# USB_Hub.net
KiCad netlist of a schematic drawn in Altium Designer
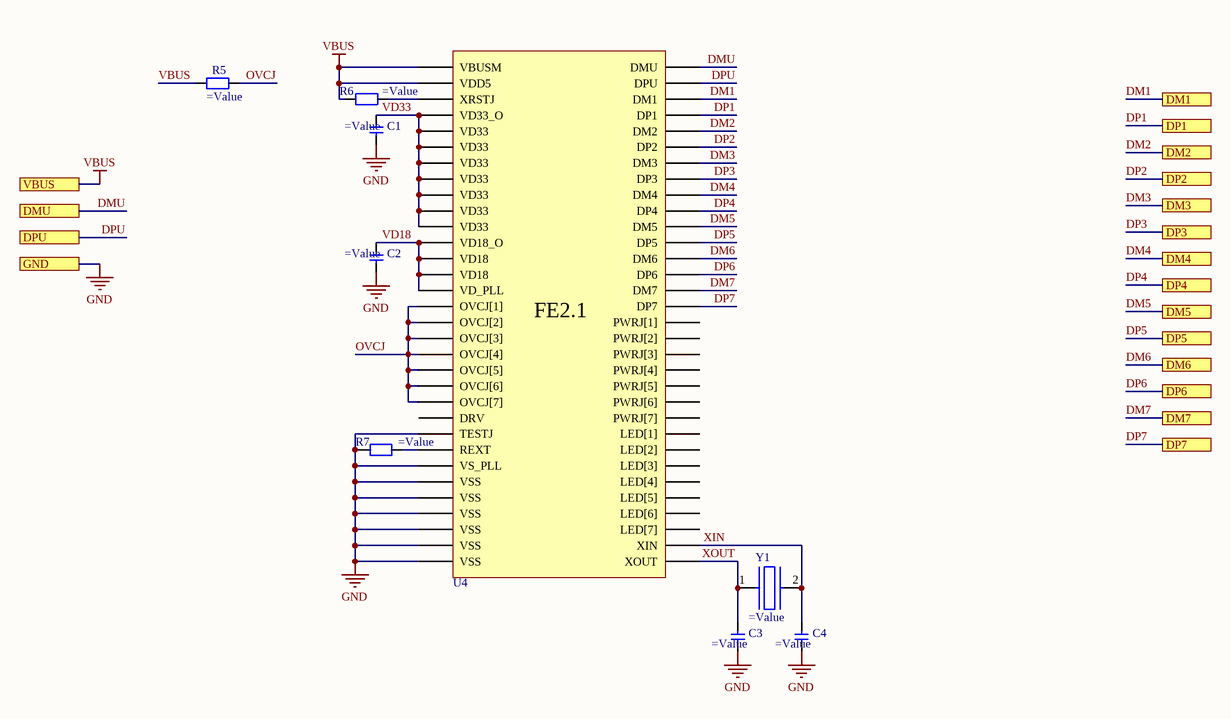
[diagram p0: USB Hub.SchDoc]

(export (version "E")
  (design (tool "Eeschema 10.0.6"))
  (components
    (comp (ref "C1") (value "~") (footprint "cap0402") (libsource (lib "AlexChistiakov") (part "Cap SMD")))
    (comp (ref "C2") (value "~") (footprint "cap0402") (libsource (lib "AlexChistiakov") (part "Cap SMD")))
    (comp (ref "C3") (value "~") (footprint "cap0402") (libsource (lib "AlexChistiakov") (part "Cap SMD")))
    (comp (ref "C4") (value "~") (footprint "cap0402") (libsource (lib "AlexChistiakov") (part "Cap SMD")))
    (comp (ref "R5")
      (value "~")
      (footprint "res0402")
      (libsource (lib "AlexChistiakov") (part "Resistor SMD"))
    )
    (comp (ref "R6")
      (value "~")
      (footprint "res0402")
      (libsource (lib "AlexChistiakov") (part "Resistor SMD"))
    )
    (comp (ref "R7")
      (value "~")
      (footprint "res0402")
      (libsource (lib "AlexChistiakov") (part "Resistor SMD"))
    )
    (comp (ref "U4")
      (value "FE2.1")
      (footprint "LQFP64_N_1")
      (libsource (lib "AlexChistiakov") (part "FE2.1"))
    )
    (comp (ref "Y1")
      (value "~")
      (footprint "QSMD3.2x2.5_A")
      (libsource (lib "AlexChistiakov") (part "Quartz"))
    )
  )
  (nets
    (net (code "1") (name "/DM1") (class "Default")
      (node (ref "U4") (pin "26") (pinfunction "DM1_26") (pintype "passive"))
    )
    (net (code "2") (name "/DM2") (class "Default")
      (node (ref "U4") (pin "23") (pinfunction "DM2_23") (pintype "passive"))
    )
    (net (code "3") (name "/DM3") (class "Default")
      (node (ref "U4") (pin "20") (pinfunction "DM3_20") (pintype "passive"))
    )
    (net (code "4") (name "/DM4") (class "Default")
      (node (ref "U4") (pin "17") (pinfunction "DM4_17") (pintype "passive"))
    )
    (net (code "5") (name "/DM5") (class "Default")
      (node (ref "U4") (pin "41") (pinfunction "DM5_41") (pintype "passive"))
    )
    (net (code "6") (name "/DM6") (class "Default")
      (node (ref "U4") (pin "44") (pinfunction "DM6_44") (pintype "passive"))
    )
    (net (code "7") (name "/DM7") (class "Default")
      (node (ref "U4") (pin "47") (pinfunction "DM7_47") (pintype "passive"))
    )
    (net (code "8") (name "/DMU") (class "Default")
      (node (ref "U4") (pin "38") (pinfunction "DMU_38") (pintype "passive"))
    )
    (net (code "9") (name "/DP1") (class "Default")
      (node (ref "U4") (pin "27") (pinfunction "DP1_27") (pintype "passive"))
    )
    (net (code "10") (name "/DP2") (class "Default")
      (node (ref "U4") (pin "24") (pinfunction "DP2_24") (pintype "passive"))
    )
    (net (code "11") (name "/DP3") (class "Default")
      (node (ref "U4") (pin "21") (pinfunction "DP3_21") (pintype "passive"))
    )
    (net (code "12") (name "/DP4") (class "Default")
      (node (ref "U4") (pin "18") (pinfunction "DP4_18") (pintype "passive"))
    )
    (net (code "13") (name "/DP5") (class "Default")
      (node (ref "U4") (pin "42") (pinfunction "DP5_42") (pintype "passive"))
    )
    (net (code "14") (name "/DP6") (class "Default")
      (node (ref "U4") (pin "45") (pinfunction "DP6_45") (pintype "passive"))
    )
    (net (code "15") (name "/DP7") (class "Default")
      (node (ref "U4") (pin "48") (pinfunction "DP7_48") (pintype "passive"))
    )
    (net (code "16") (name "/DPU") (class "Default")
      (node (ref "U4") (pin "39") (pinfunction "DPU_39") (pintype "passive"))
    )
    (net (code "17") (name "/OVCJ") (class "Default")
      (node (ref "R5") (pin "2") (pinfunction "2_2") (pintype "passive"))
      (node (ref "U4") (pin "13") (pinfunction "OVCJ[3]_13") (pintype "passive"))
      (node (ref "U4") (pin "15") (pinfunction "OVCJ[4]_15") (pintype "passive"))
      (node (ref "U4") (pin "53") (pinfunction "OVCJ[7]_53") (pintype "passive"))
      (node (ref "U4") (pin "55") (pinfunction "OVCJ[6]_55") (pintype "passive"))
      (node (ref "U4") (pin "58") (pinfunction "OVCJ[5]_58") (pintype "passive"))
      (node (ref "U4") (pin "60") (pinfunction "OVCJ[1]_60") (pintype "passive"))
      (node (ref "U4") (pin "62") (pinfunction "OVCJ[2]_62") (pintype "passive"))
    )
    (net (code "18") (name "/VD18") (class "Default")
      (node (ref "C2") (pin "2") (pinfunction "2_2") (pintype "passive"))
      (node (ref "U4") (pin "29") (pinfunction "VD_PLL_29") (pintype "passive"))
      (node (ref "U4") (pin "33") (pinfunction "VD18_O_33") (pintype "passive"))
      (node (ref "U4") (pin "36") (pinfunction "VD18_36") (pintype "passive"))
      (node (ref "U4") (pin "7") (pinfunction "VD18_7") (pintype "passive"))
    )
    (net (code "19") (name "/VD33") (class "Default")
      (node (ref "C1") (pin "2") (pinfunction "2_2") (pintype "passive"))
      (node (ref "U4") (pin "10") (pinfunction "VD33_O_10") (pintype "passive"))
      (node (ref "U4") (pin "16") (pinfunction "VD33_16") (pintype "passive"))
      (node (ref "U4") (pin "22") (pinfunction "VD33_22") (pintype "passive"))
      (node (ref "U4") (pin "28") (pinfunction "VD33_28") (pintype "passive"))
      (node (ref "U4") (pin "34") (pinfunction "VD33_34") (pintype "passive"))
      (node (ref "U4") (pin "40") (pinfunction "VD33_40") (pintype "passive"))
      (node (ref "U4") (pin "46") (pinfunction "VD33_46") (pintype "passive"))
      (node (ref "U4") (pin "56") (pinfunction "VD33_56") (pintype "passive"))
    )
    (net (code "20") (name "/XIN") (class "Default")
      (node (ref "C4") (pin "2") (pinfunction "2_2") (pintype "passive"))
      (node (ref "U4") (pin "30") (pinfunction "XIN_30") (pintype "passive"))
      (node (ref "Y1") (pin "2") (pintype "power_in"))
    )
    (net (code "21") (name "/XOUT") (class "Default")
      (node (ref "C3") (pin "2") (pinfunction "2_2") (pintype "passive"))
      (node (ref "U4") (pin "31") (pinfunction "XOUT_31") (pintype "passive"))
      (node (ref "Y1") (pin "1") (pintype "power_in"))
    )
    (net (code "22") (name "GND") (class "Default")
      (node (ref "C1") (pin "1") (pinfunction "1_1") (pintype "passive"))
      (node (ref "C2") (pin "1") (pinfunction "1_1") (pintype "passive"))
      (node (ref "C3") (pin "1") (pinfunction "1_1") (pintype "passive"))
      (node (ref "C4") (pin "1") (pinfunction "1_1") (pintype "passive"))
      (node (ref "R7") (pin "1") (pinfunction "1_1") (pintype "passive"))
      (node (ref "U4") (pin "11") (pinfunction "VSS_11") (pintype "passive"))
      (node (ref "U4") (pin "19") (pinfunction "VSS_19") (pintype "passive"))
      (node (ref "U4") (pin "25") (pinfunction "VSS_25") (pintype "passive"))
      (node (ref "U4") (pin "3") (pinfunction "TESTJ_3") (pintype "passive"))
      (node (ref "U4") (pin "32") (pinfunction "VS_PLL_32") (pintype "passive"))
      (node (ref "U4") (pin "37") (pinfunction "VSS_37") (pintype "passive"))
      (node (ref "U4") (pin "43") (pinfunction "VSS_43") (pintype "passive"))
      (node (ref "U4") (pin "49") (pinfunction "VSS_49") (pintype "passive"))
    )
    (net (code "23") (name "Net-(U4-REXT)") (class "Default")
      (node (ref "R7") (pin "2") (pinfunction "2_2") (pintype "passive"))
      (node (ref "U4") (pin "35") (pinfunction "REXT_35") (pintype "passive"))
    )
    (net (code "24") (name "Net-(U4-XRSTJ)") (class "Default")
      (node (ref "R6") (pin "2") (pinfunction "2_2") (pintype "passive"))
      (node (ref "U4") (pin "50") (pinfunction "XRSTJ_50") (pintype "passive"))
    )
    (net (code "25") (name "VBUS") (class "Default")
      (node (ref "R5") (pin "1") (pinfunction "1_1") (pintype "passive"))
      (node (ref "R6") (pin "1") (pinfunction "1_1") (pintype "passive"))
      (node (ref "U4") (pin "51") (pinfunction "VBUSM_51") (pintype "passive"))
      (node (ref "U4") (pin "9") (pinfunction "VDD5_9") (pintype "passive"))
    )
    (net (code "26") (name "unconnected-(U4-DRV-Pad2)") (class "Default")
      (node (ref "U4") (pin "2") (pinfunction "DRV_2") (pintype "passive"))
    )
    (net (code "27") (name "unconnected-(U4-LED[1]-Pad4)") (class "Default")
      (node (ref "U4") (pin "4") (pinfunction "LED[1]_4") (pintype "passive"))
    )
    (net (code "28") (name "unconnected-(U4-LED[2]-Pad5)") (class "Default")
      (node (ref "U4") (pin "5") (pinfunction "LED[2]_5") (pintype "passive"))
    )
    (net (code "29") (name "unconnected-(U4-LED[3]-Pad6)") (class "Default")
      (node (ref "U4") (pin "6") (pinfunction "LED[3]_6") (pintype "passive"))
    )
    (net (code "30") (name "unconnected-(U4-LED[4]-Pad8)") (class "Default")
      (node (ref "U4") (pin "8") (pinfunction "LED[4]_8") (pintype "passive"))
    )
    (net (code "31") (name "unconnected-(U4-LED[5]-Pad1)") (class "Default")
      (node (ref "U4") (pin "1") (pinfunction "LED[5]_1") (pintype "passive"))
    )
    (net (code "32") (name "unconnected-(U4-LED[6]-Pad64)") (class "Default")
      (node (ref "U4") (pin "64") (pinfunction "LED[6]_64") (pintype "passive"))
    )
    (net (code "33") (name "unconnected-(U4-LED[7]-Pad63)") (class "Default")
      (node (ref "U4") (pin "63") (pinfunction "LED[7]_63") (pintype "passive"))
    )
    (net (code "34") (name "unconnected-(U4-PWRJ[1]-Pad59)") (class "Default")
      (node (ref "U4") (pin "59") (pinfunction "PWRJ[1]_59") (pintype "passive"))
    )
    (net (code "35") (name "unconnected-(U4-PWRJ[2]-Pad61)") (class "Default")
      (node (ref "U4") (pin "61") (pinfunction "PWRJ[2]_61") (pintype "passive"))
    )
    (net (code "36") (name "unconnected-(U4-PWRJ[3]-Pad12)") (class "Default")
      (node (ref "U4") (pin "12") (pinfunction "PWRJ[3]_12") (pintype "passive"))
    )
    (net (code "37") (name "unconnected-(U4-PWRJ[4]-Pad14)") (class "Default")
      (node (ref "U4") (pin "14") (pinfunction "PWRJ[4]_14") (pintype "passive"))
    )
    (net (code "38") (name "unconnected-(U4-PWRJ[5]-Pad57)") (class "Default")
      (node (ref "U4") (pin "57") (pinfunction "PWRJ[5]_57") (pintype "passive"))
    )
    (net (code "39") (name "unconnected-(U4-PWRJ[6]-Pad54)") (class "Default")
      (node (ref "U4") (pin "54") (pinfunction "PWRJ[6]_54") (pintype "passive"))
    )
    (net (code "40") (name "unconnected-(U4-PWRJ[7]-Pad52)") (class "Default")
      (node (ref "U4") (pin "52") (pinfunction "PWRJ[7]_52") (pintype "passive"))
    )
  )
)
